# Servo_Connector.net
KiCad netlist of a schematic drawn in Altium Designer
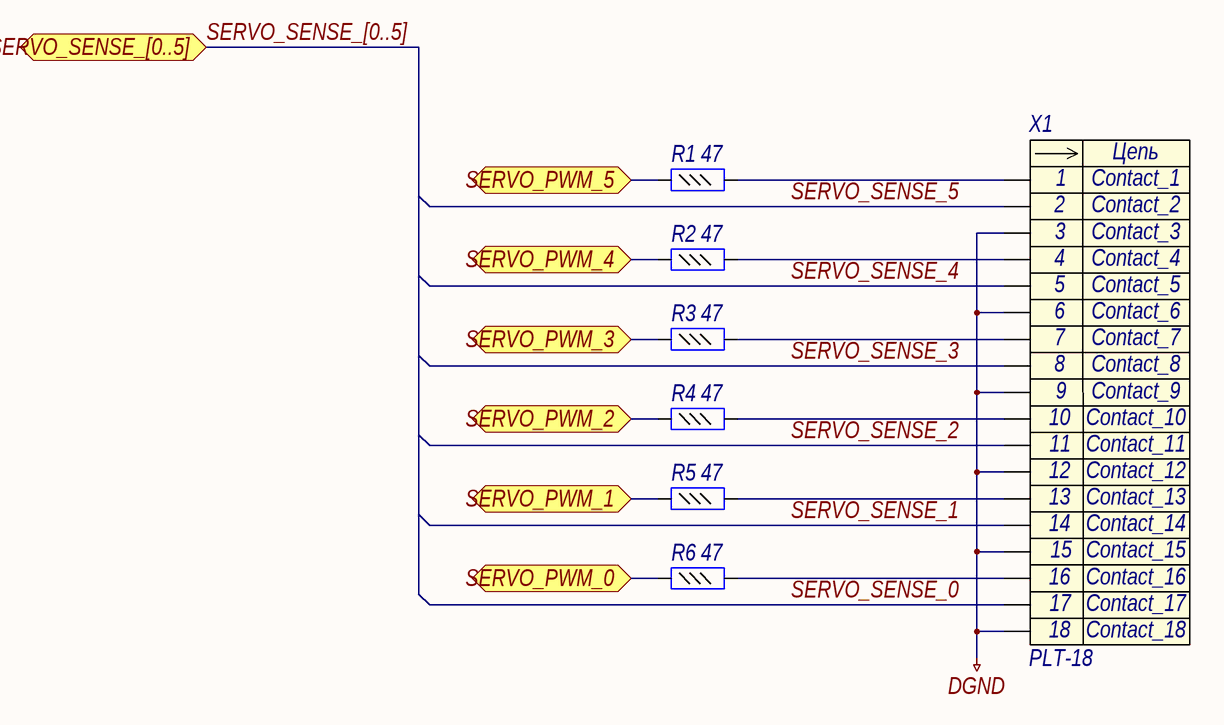
[diagram p0: Servo_Connector.SchDoc]

(export (version "E")
  (design (tool "Eeschema 10.0.6"))
  (components
    (comp (ref "R1")
      (value "47")
      (footprint "R0603")
      (description "Резистор")
      (fields (field (name "PART NUMBER") "RC0603FR-0747RL") (field (name "POWER") "0,062Вт"))
      (libsource (lib "MOP44") (part "Resistor_0,062Вт"))
    )
    (comp (ref "R2")
      (value "47")
      (footprint "R0603")
      (description "Резистор")
      (fields (field (name "PART NUMBER") "RC0603FR-0747RL") (field (name "POWER") "0,062Вт"))
      (libsource (lib "MOP44") (part "Resistor_0,062Вт"))
    )
    (comp (ref "R3")
      (value "47")
      (footprint "R0603")
      (description "Резистор")
      (fields (field (name "PART NUMBER") "RC0603FR-0747RL") (field (name "POWER") "0,062Вт"))
      (libsource (lib "MOP44") (part "Resistor_0,062Вт"))
    )
    (comp (ref "R4")
      (value "47")
      (footprint "R0603")
      (description "Резистор")
      (fields (field (name "PART NUMBER") "RC0603FR-0747RL") (field (name "POWER") "0,062Вт"))
      (libsource (lib "MOP44") (part "Resistor_0,062Вт"))
    )
    (comp (ref "R5")
      (value "47")
      (footprint "R0603")
      (description "Резистор")
      (fields (field (name "PART NUMBER") "RC0603FR-0747RL") (field (name "POWER") "0,062Вт"))
      (libsource (lib "MOP44") (part "Resistor_0,062Вт"))
    )
    (comp (ref "R6")
      (value "47")
      (footprint "R0603")
      (description "Резистор")
      (fields (field (name "PART NUMBER") "RC0603FR-0747RL") (field (name "POWER") "0,062Вт"))
      (libsource (lib "MOP44") (part "Resistor_0,062Вт"))
    )
    (comp (ref "X1")
      (value "PLT-18")
      (footprint "PLT-18")
      (description "Разъем - 18 конт. вилка")
      (fields (field (name "PART NUMBER") "PLT-81"))
      (libsource (lib "MOP44") (part "Header_18_plg"))
    )
  )
  (nets
    (net (code "1") (name "/SERVO_PWM_0") (class "Default")
      (node (ref "R6") (pin "1") (pinfunction "1_1") (pintype "passive"))
    )
    (net (code "2") (name "/SERVO_PWM_1") (class "Default")
      (node (ref "R5") (pin "1") (pinfunction "1_1") (pintype "passive"))
    )
    (net (code "3") (name "/SERVO_PWM_2") (class "Default")
      (node (ref "R4") (pin "1") (pinfunction "1_1") (pintype "passive"))
    )
    (net (code "4") (name "/SERVO_PWM_3") (class "Default")
      (node (ref "R3") (pin "1") (pinfunction "1_1") (pintype "passive"))
    )
    (net (code "5") (name "/SERVO_PWM_4") (class "Default")
      (node (ref "R2") (pin "1") (pinfunction "1_1") (pintype "passive"))
    )
    (net (code "6") (name "/SERVO_PWM_5") (class "Default")
      (node (ref "R1") (pin "1") (pinfunction "1_1") (pintype "passive"))
    )
    (net (code "7") (name "/SERVO_SENSE_0") (class "Default")
      (node (ref "X1") (pin "17") (pinfunction "17_17") (pintype "passive"))
    )
    (net (code "8") (name "/SERVO_SENSE_1") (class "Default")
      (node (ref "X1") (pin "14") (pinfunction "14_14") (pintype "passive"))
    )
    (net (code "9") (name "/SERVO_SENSE_2") (class "Default")
      (node (ref "X1") (pin "11") (pinfunction "11_11") (pintype "passive"))
    )
    (net (code "10") (name "/SERVO_SENSE_3") (class "Default")
      (node (ref "X1") (pin "8") (pinfunction "8_8") (pintype "passive"))
    )
    (net (code "11") (name "/SERVO_SENSE_4") (class "Default")
      (node (ref "X1") (pin "5") (pinfunction "5_5") (pintype "passive"))
    )
    (net (code "12") (name "/SERVO_SENSE_5") (class "Default")
      (node (ref "X1") (pin "2") (pinfunction "2_2") (pintype "passive"))
    )
    (net (code "14") (name "DGND") (class "Default")
      (node (ref "X1") (pin "12") (pinfunction "12_12") (pintype "passive"))
      (node (ref "X1") (pin "15") (pinfunction "15_15") (pintype "passive"))
      (node (ref "X1") (pin "18") (pinfunction "18_18") (pintype "passive"))
      (node (ref "X1") (pin "3") (pinfunction "3_3") (pintype "passive"))
      (node (ref "X1") (pin "6") (pinfunction "6_6") (pintype "passive"))
      (node (ref "X1") (pin "9") (pinfunction "9_9") (pintype "passive"))
    )
    (net (code "15") (name "Net-(R1-Pad2)") (class "Default")
      (node (ref "R1") (pin "2") (pinfunction "2_2") (pintype "passive"))
      (node (ref "X1") (pin "1") (pinfunction "1_1") (pintype "passive"))
    )
    (net (code "16") (name "Net-(R2-Pad2)") (class "Default")
      (node (ref "R2") (pin "2") (pinfunction "2_2") (pintype "passive"))
      (node (ref "X1") (pin "4") (pinfunction "4_4") (pintype "passive"))
    )
    (net (code "17") (name "Net-(R3-Pad2)") (class "Default")
      (node (ref "R3") (pin "2") (pinfunction "2_2") (pintype "passive"))
      (node (ref "X1") (pin "7") (pinfunction "7_7") (pintype "passive"))
    )
    (net (code "18") (name "Net-(R4-Pad2)") (class "Default")
      (node (ref "R4") (pin "2") (pinfunction "2_2") (pintype "passive"))
      (node (ref "X1") (pin "10") (pinfunction "10_10") (pintype "passive"))
    )
    (net (code "19") (name "Net-(R5-Pad2)") (class "Default")
      (node (ref "R5") (pin "2") (pinfunction "2_2") (pintype "passive"))
      (node (ref "X1") (pin "13") (pinfunction "13_13") (pintype "passive"))
    )
    (net (code "20") (name "Net-(R6-Pad2)") (class "Default")
      (node (ref "R6") (pin "2") (pinfunction "2_2") (pintype "passive"))
      (node (ref "X1") (pin "16") (pinfunction "16_16") (pintype "passive"))
    )
  )
)
